# ATMega328P_weather_station_MCU.net
KiCad netlist of a schematic drawn in Altium Designer
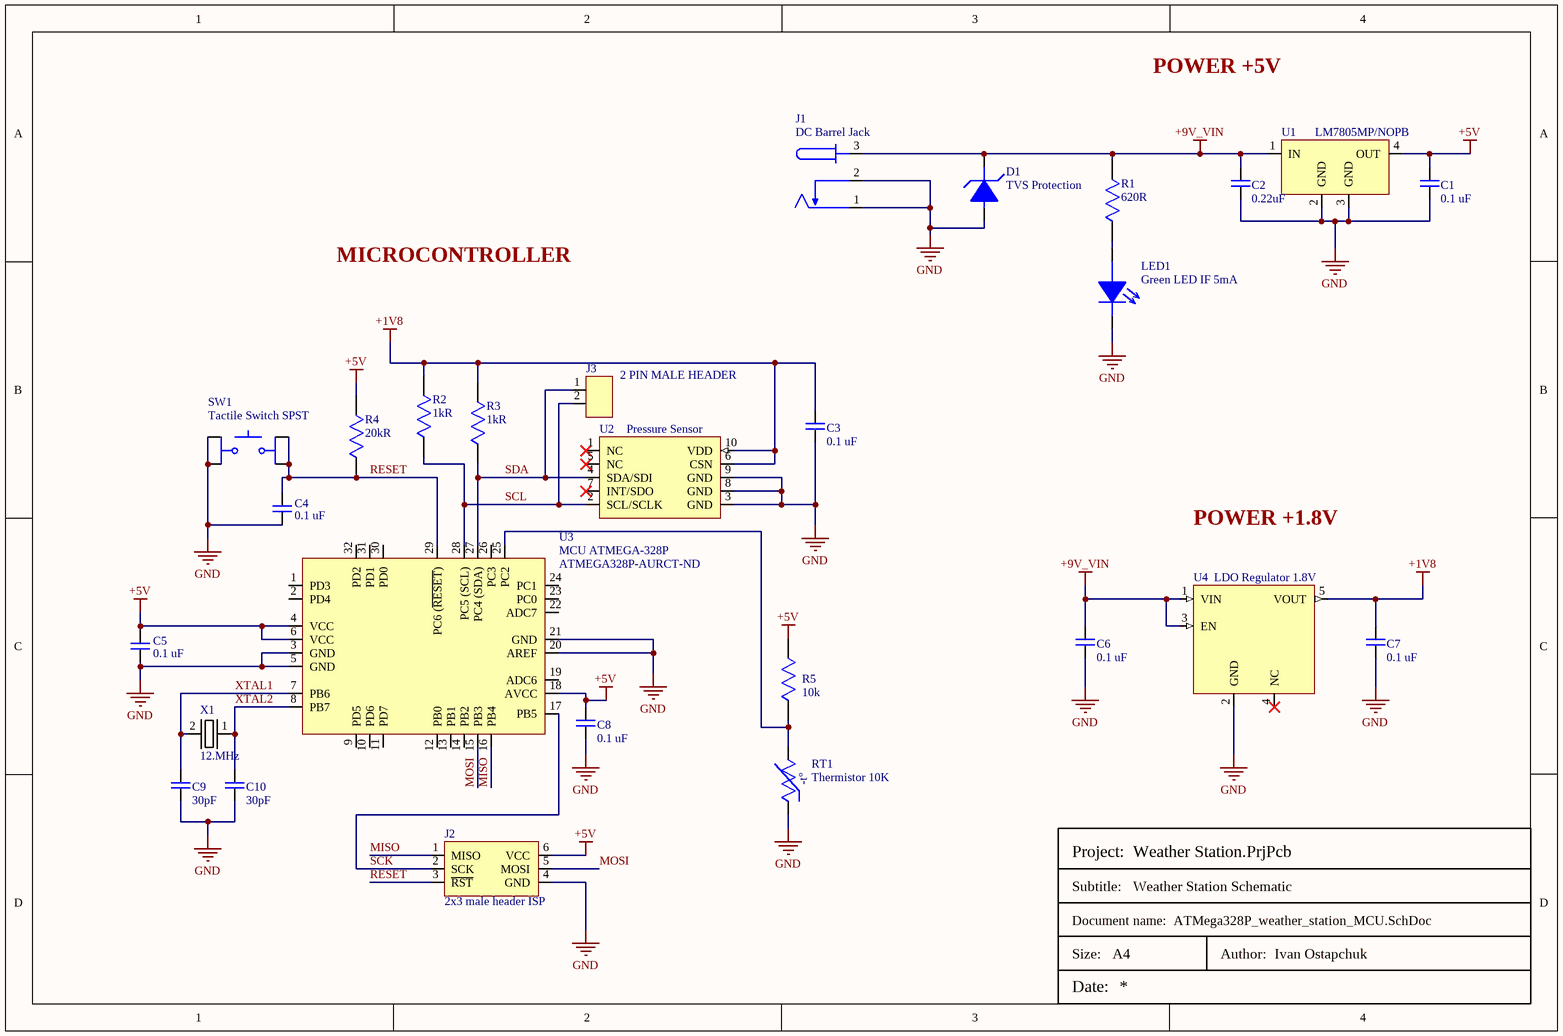
[diagram p0: ATMega328P_weather_station_MCU.SchDoc]

(export (version "E")
  (design (tool "Eeschema 10.0.6"))
  (components
    (comp (ref "*")
      (value "Title Block")
      (description "Custom schematic title block")
      (fields (field (name "SUBTITLE") "Weather Station Schematic") (field (name "SIZE") "A4"))
      (libsource (lib "Weather_Schlib") (part "Title Block"))
    )
    (comp (ref "C1")
      (value "0.1 uF")
      (footprint "1210B104K500CT")
      (fields
        (field (name "MANUFACTURER") "Walsin Technologies")
        (field (name "MANUFACTURER PART NUMBER") "1210B104K500CT")
        (field (name "TOLERANCE") "10%")
      )
      (libsource (lib "Weather_Schlib") (part "Ceramic Cap, 0.1 uF, 10%, 50 V, 1210"))
    )
    (comp (ref "C2")
      (value "0.22uF")
      (footprint "Ceramic Cap 0.22uF 1210 Low density")
      (description "Multilayer Ceramic Capacitors MLCC - SMD/SMT 50V 0.22uF X7R 1210 10%")
      (fields
        (field (name "MANUFACTURER") "KEMET")
        (field (name "MANUFACTURER PART NUMBER") "C1210C224K5RACTU")
      )
      (libsource (lib "Weather_Schlib") (part "Ceramic Cap, 0.22uF, 10%, 50V, 1210"))
    )
    (comp (ref "C3")
      (value "0.1 uF")
      (footprint "1210B104K500CT")
      (fields
        (field (name "MANUFACTURER") "Walsin Technologies")
        (field (name "MANUFACTURER PART NUMBER") "1210B104K500CT")
        (field (name "TOLERANCE") "10%")
      )
      (libsource (lib "Weather_Schlib") (part "Ceramic Cap, 0.1 uF, 10%, 50 V, 1210"))
    )
    (comp (ref "C4")
      (value "0.1 uF")
      (footprint "1210B104K500CT")
      (fields
        (field (name "MANUFACTURER") "Walsin Technologies")
        (field (name "MANUFACTURER PART NUMBER") "1210B104K500CT")
        (field (name "TOLERANCE") "10%")
      )
      (libsource (lib "Weather_Schlib") (part "Ceramic Cap, 0.1 uF, 10%, 50 V, 1210"))
    )
    (comp (ref "C5")
      (value "0.1 uF")
      (footprint "1210B104K500CT")
      (fields
        (field (name "MANUFACTURER") "Walsin Technologies")
        (field (name "MANUFACTURER PART NUMBER") "1210B104K500CT")
        (field (name "TOLERANCE") "10%")
      )
      (libsource (lib "Weather_Schlib") (part "Ceramic Cap, 0.1 uF, 10%, 50 V, 1210"))
    )
    (comp (ref "C6")
      (value "0.1 uF")
      (footprint "1210B104K500CT")
      (fields
        (field (name "MANUFACTURER") "Walsin Technologies")
        (field (name "MANUFACTURER PART NUMBER") "1210B104K500CT")
        (field (name "TOLERANCE") "10%")
      )
      (libsource (lib "Weather_Schlib") (part "Ceramic Cap, 0.1 uF, 10%, 50 V, 1210"))
    )
    (comp (ref "C7")
      (value "0.1 uF")
      (footprint "1210B104K500CT")
      (fields
        (field (name "MANUFACTURER") "Walsin Technologies")
        (field (name "MANUFACTURER PART NUMBER") "1210B104K500CT")
        (field (name "TOLERANCE") "10%")
      )
      (libsource (lib "Weather_Schlib") (part "Ceramic Cap, 0.1 uF, 10%, 50 V, 1210"))
    )
    (comp (ref "C8")
      (value "0.1 uF")
      (footprint "1210B104K500CT")
      (fields
        (field (name "MANUFACTURER") "Walsin Technologies")
        (field (name "MANUFACTURER PART NUMBER") "1210B104K500CT")
        (field (name "TOLERANCE") "10%")
      )
      (libsource (lib "Weather_Schlib") (part "Ceramic Cap, 0.1 uF, 10%, 50 V, 1210"))
    )
    (comp (ref "C9")
      (value "30pF")
      (footprint "Kyocera 1210 Ceramic Capacitor")
      (description "30 pF ±5% 200V Ceramic Capacitor C0G, NP0 1210 (3225 Metric)")
      (fields
        (field (name "MANUFACTURER") "Kyocera AVX")
        (field (name "MANUFACTURER PART NUMBER") "KGQ32DCG2D300JT")
      )
      (libsource (lib "Weather_Schlib") (part "Ceramic Cap, 30pF, ±5%, 200V, 1210"))
    )
    (comp (ref "C10")
      (value "30pF")
      (footprint "Kyocera 1210 Ceramic Capacitor")
      (description "30 pF ±5% 200V Ceramic Capacitor C0G, NP0 1210 (3225 Metric)")
      (fields
        (field (name "MANUFACTURER") "Kyocera AVX")
        (field (name "MANUFACTURER PART NUMBER") "KGQ32DCG2D300JT")
      )
      (libsource (lib "Weather_Schlib") (part "Ceramic Cap, 30pF, ±5%, 200V, 1210"))
    )
    (comp (ref "D1")
      (value "TVS Protection")
      (footprint "Unidirectional TVS protection diode")
      (fields (field (name "MANUFACTURER") "Littelfuse") (field (name "MANUFACTURER PART NUMBER") "SMAJ10A"))
      (libsource (lib "Weather_Schlib") (part "Unidirectional TVS protection Diode"))
    )
    (comp (ref "J1")
      (value "DC Barrel Jack")
      (footprint "Power Barrel Jack")
      (description "Power Barrel Connector Jack 2.05mm ID (0.081\"), 5.50mm OD (0.217\") Surface Mount, Right Angle")
      (fields
        (field (name "MANUFACTURER") "Global Connector Technology")
        (field (name "MANUFACTURER PART NUMBER") "DCJ200-05-A-K1-A")
      )
      (libsource (lib "Weather_Schlib") (part "Barrel Connector Jack"))
    )
    (comp (ref "J2")
      (value "2x3 male header ISP")
      (footprint "2x3 male header ISP")
      (description "Bs Dr Vt SMT Hdr 2X3 TR-10125394-T0803ALF ¦ Amphenol Fci (amphenol Cs) 10125394T0803ALF")
      (fields
        (field (name "MANUFACTURER") "Amphenol Communications Solutions")
        (field (name "MANUFACTURER PART NUMBER") "10125394-T0803ALF")
      )
      (libsource (lib "Weather_Schlib") (part "2x3 male header ISP"))
    )
    (comp (ref "J3")
      (value "2 PIN MALE HEADER")
      (footprint "2 pin male header smd")
      (description "Conn Unshrouded Header HDR 2 POS 2.54mm Solder ST SMD Automotive T/R")
      (fields
        (field (name "MANUFACTURER") "Samtec")
        (field (name "MANUFACTURER PART NUMBER") "TSM-102-01-T-SV-TR")
      )
      (libsource (lib "Weather_Schlib") (part "2 pin male header"))
    )
    (comp (ref "LED1")
      (value "Green LED IF 5mA")
      (footprint "SMD LED")
      (description "Side View / 0805 / 2.1 X 1.0 X 0")
      (fields (field (name "MANUFACTURER") "Inolux") (field (name "MANUFACTURER PART NUMBER") "IN-S85CS5G"))
      (libsource (lib "Weather_Schlib") (part "Green LED IF 5mA"))
    )
    (comp (ref "R1")
      (value "620R")
      (footprint "1206 WIDE SMD Resistor")
      (fields
        (field (name "MANUFACTURER") "Rohm")
        (field (name "MANUFACTURER PART NUMBER") "LTR18EZPF6200")
        (field (name "TOLERANCE") "1%")
      )
      (libsource (lib "Weather_Schlib") (part "SMD Resistor 620 Ohms, 1.5W 1206 WIDE"))
    )
    (comp (ref "R2")
      (value "1kR")
      (footprint "Yageo 1206 SMD Resistor")
      (description "SMD Chip Resistor, 1 kOhm, ± 1%, 250 mW, 1206 [3216 Metric], Thick Film, General Purpose")
      (fields
        (field (name "MANUFACTURER") "Yageo")
        (field (name "MANUFACTURER PART NUMBER") "RC1206FR-071KL")
      )
      (libsource (lib "Weather_Schlib") (part "SMD Resistor 1 kOhm, 250mW, 1206"))
    )
    (comp (ref "R3")
      (value "1kR")
      (footprint "Yageo 1206 SMD Resistor")
      (description "SMD Chip Resistor, 1 kOhm, ± 1%, 250 mW, 1206 [3216 Metric], Thick Film, General Purpose")
      (fields
        (field (name "MANUFACTURER") "Yageo")
        (field (name "MANUFACTURER PART NUMBER") "RC1206FR-071KL")
      )
      (libsource (lib "Weather_Schlib") (part "SMD Resistor 1 kOhm, 250mW, 1206"))
    )
    (comp (ref "R4")
      (value "20kR")
      (footprint "Yageo 1206 SMD Resistor")
      (description "20 kOhm, ± 1%, 250 mW, SMD Resistor, 1206 [3216 Metric], Thick Film, General Purpose")
      (fields
        (field (name "MANUFACTURER") "Yageo")
        (field (name "MANUFACTURER PART NUMBER") "RC1206FR-0720KL")
      )
      (libsource (lib "Weather_Schlib") (part "SMD Resistor, 20k Ohm, 250mW, 1206"))
    )
    (comp (ref "R5")
      (value "10k")
      (footprint "Yageo 1206 SMD Resistor")
      (description "SMD Chip Resistor, 10 kOhm, 1%, 250 mW, 1206 [3216 Metric], Thick Film, General Purpose")
      (fields
        (field (name "MANUFACTURER") "Yageo")
        (field (name "MANUFACTURER PART NUMBER") "RC1206FR-0710KL")
      )
      (libsource (lib "Weather_Schlib") (part "SMD Resistor, 10 kOhm, 250 mW, 1206"))
    )
    (comp (ref "RT1")
      (value "Thermistor 10K")
      (footprint "Yageo 1206 SMD Resistor")
      (description "Thermistor NTC 10K Ohm 10% 2-Pin 1206 Surface Mount Solder Pad 3510K Blister T/R")
      (fields
        (field (name "MANUFACTURER") "TDK EPCOS")
        (field (name "MANUFACTURER PART NUMBER") "B57621C5103K062")
      )
      (libsource (lib "Weather_Schlib") (part "Thermistor NTC 10K"))
    )
    (comp (ref "SW1")
      (value "Tactile Switch SPST")
      (footprint "Tactile Switch")
      (description "TL3305A Series SPST 12 V 4.5 x 4.5 mm 260 gf Top Actuated SMT Tactile Switch")
      (fields
        (field (name "MANUFACTURER") "E-Switch")
        (field (name "MANUFACTURER PART NUMBER") "TL3305AF260QG")
      )
      (libsource (lib "Weather_Schlib") (part "Tactile Switch SPST"))
    )
    (comp (ref "U1")
      (value "Linear V Regulator")
      (footprint "LM7805MP/NOPB")
      (description "1.5-A, 30-V, linear voltage regulator 4-SOT-223 0 to 125")
      (fields
        (field (name "MANUFACTURER") "Texas Instruments")
        (field (name "MANUFACTURER PART NUMBER") "LM7805MP/NOPB")
      )
      (libsource (lib "Weather_Schlib") (part "Linear Voltage Regulator LM7805MP/NOPB"))
    )
    (comp (ref "U2")
      (value "Pressure Sensor")
      (footprint "XDCR_ENS220S-BLGT")
      (description "Pressure Sensor 4.35PSI ~ 17.4PSI (30kPa ~ 120kPa) Absolute 24 b 10-LGA")
      (fields
        (field (name "MANUFACTURER") "ScioSense")
        (field (name "MANUFACTURER PART NUMBER") "ENS220S-BLGT")
      )
      (libsource (lib "Weather_Schlib") (part "Pressure Sensor"))
    )
    (comp (ref "U3")
      (value "MCU ATMEGA-328P")
      (footprint "QFP80P900X900X120-32N")
      (description "AVR series Microcontroller IC 8-Bit 2MHz 32KB (16K x 16) FLASH 32-TQFP (7x7)")
      (fields
        (field (name "MANUFACTURER") "Microchip")
        (field (name "MANUFACTURER PART NUMBER") "ATMEGA328P-AUR")
        (field (name "SUPPLIER PART NUMBER 1") "ATMEGA328P-AURCT-ND")
      )
      (libsource (lib "Weather_Schlib") (part "MCU ATMEGA-328P"))
    )
    (comp (ref "U4")
      (value "LDO Regulator 1.8V")
      (footprint "LDO 1.8V")
      (description "Linear Voltage Regulator IC Positive Fixed 1 Output 1.8V 300mA SOT-23-5")
      (fields
        (field (name "MANUFACTURER") "Microchip")
        (field (name "MANUFACTURER PART NUMBER") "MIC5504-1.8YM5-TR")
      )
      (libsource (lib "Weather_Schlib") (part "LDO Regulator 1.8V"))
    )
    (comp (ref "X1")
      (value "12.MHz")
      (footprint "ABLS-12.000MHZ-20-B-3-H-T")
      (description "Crystal 12MHz ±25ppm (Tol) ±35ppm (Stability) 20pF FUND 50Ohm 2-Pin HC-49/US SMD T/R")
      (fields
        (field (name "MANUFACTURER") "Abracon")
        (field (name "MANUFACTURER PART NUMBER") "ABLS-12.000MHZ-20-B-3-H-T")
      )
      (libsource (lib "Weather_Schlib") (part "ABLS-12.000MHZ-20-B-3-H-T"))
    )
  )
  (nets
    (net (code "1") (name "+1V8") (class "Default")
      (node (ref "C3") (pin "2") (pinfunction "2_2") (pintype "passive"))
      (node (ref "C7") (pin "1") (pinfunction "1_1") (pintype "passive"))
      (node (ref "R2") (pin "1") (pinfunction "1_1") (pintype "passive"))
      (node (ref "R3") (pin "1") (pinfunction "1_1") (pintype "passive"))
      (node (ref "U2") (pin "10") (pinfunction "VDD_10") (pintype "input"))
      (node (ref "U2") (pin "6") (pinfunction "CSN_6") (pintype "passive"))
      (node (ref "U4") (pin "5") (pinfunction "VOUT_5") (pintype "output"))
    )
    (net (code "2") (name "+5V") (class "Default")
      (node (ref "C1") (pin "1") (pinfunction "1_1") (pintype "passive"))
      (node (ref "C5") (pin "2") (pinfunction "2_2") (pintype "passive"))
      (node (ref "C8") (pin "2") (pinfunction "2_2") (pintype "passive"))
      (node (ref "J2") (pin "6") (pinfunction "VCC_6") (pintype "passive"))
      (node (ref "R4") (pin "1") (pinfunction "1_1") (pintype "passive"))
      (node (ref "R5") (pin "1") (pinfunction "1_1") (pintype "passive"))
      (node (ref "U1") (pin "4") (pinfunction "OUT_4") (pintype "passive"))
      (node (ref "U3") (pin "18") (pinfunction "AVCC_18") (pintype "passive"))
      (node (ref "U3") (pin "4") (pinfunction "VCC_4") (pintype "passive"))
      (node (ref "U3") (pin "6") (pinfunction "VCC_6") (pintype "passive"))
    )
    (net (code "3") (name "+9V_VIN") (class "Default")
      (node (ref "C2") (pin "1") (pinfunction "1_1") (pintype "passive"))
      (node (ref "C6") (pin "1") (pinfunction "1_1") (pintype "passive"))
      (node (ref "D1") (pin "2") (pinfunction "2_2") (pintype "passive"))
      (node (ref "J1") (pin "3") (pinfunction "CENTER_(V+)_3") (pintype "power_in"))
      (node (ref "R1") (pin "2") (pinfunction "2_2") (pintype "passive"))
      (node (ref "U1") (pin "1") (pinfunction "IN_1") (pintype "passive"))
      (node (ref "U4") (pin "1") (pinfunction "VIN_1") (pintype "input"))
      (node (ref "U4") (pin "3") (pinfunction "EN_3") (pintype "input"))
    )
    (net (code "4") (name "/MISO") (class "Default")
      (node (ref "J2") (pin "1") (pinfunction "MISO_1") (pintype "passive"))
      (node (ref "U3") (pin "16") (pinfunction "PB4_16") (pintype "passive"))
    )
    (net (code "5") (name "/MOSI") (class "Default")
      (node (ref "J2") (pin "5") (pinfunction "MOSI_5") (pintype "passive"))
      (node (ref "U3") (pin "15") (pinfunction "PB3_15") (pintype "passive"))
    )
    (net (code "6") (name "/RESET") (class "Default")
      (node (ref "C4") (pin "2") (pinfunction "2_2") (pintype "passive"))
      (node (ref "J2") (pin "3") (pinfunction "~{RST}_3") (pintype "passive"))
      (node (ref "R4") (pin "2") (pinfunction "2_2") (pintype "passive"))
      (node (ref "SW1") (pin "2") (pinfunction "2_2") (pintype "passive"))
      (node (ref "SW1") (pin "4") (pinfunction "4_4") (pintype "passive"))
      (node (ref "U3") (pin "29") (pinfunction "PC6_(~{RESET})_29") (pintype "passive"))
    )
    (net (code "7") (name "/SCK") (class "Default")
      (node (ref "J2") (pin "2") (pinfunction "SCK_2") (pintype "passive"))
      (node (ref "U3") (pin "17") (pinfunction "PB5_17") (pintype "passive"))
    )
    (net (code "8") (name "/SCL") (class "Default")
      (node (ref "J3") (pin "2") (pintype "passive"))
      (node (ref "R2") (pin "2") (pinfunction "2_2") (pintype "passive"))
      (node (ref "U2") (pin "2") (pinfunction "SCL/SCLK_2") (pintype "passive"))
      (node (ref "U3") (pin "28") (pinfunction "PC5_(SCL)_28") (pintype "passive"))
    )
    (net (code "9") (name "/SDA") (class "Default")
      (node (ref "J3") (pin "1") (pintype "passive"))
      (node (ref "R3") (pin "2") (pinfunction "2_2") (pintype "passive"))
      (node (ref "U2") (pin "4") (pinfunction "SDA/SDI_4") (pintype "passive"))
      (node (ref "U3") (pin "27") (pinfunction "PC4_(SDA)_27") (pintype "passive"))
    )
    (net (code "10") (name "/XTAL1") (class "Default")
      (node (ref "C9") (pin "2") (pinfunction "2_2") (pintype "passive"))
      (node (ref "U3") (pin "7") (pinfunction "PB6_7") (pintype "passive"))
      (node (ref "X1") (pin "2") (pinfunction "2_2") (pintype "passive"))
    )
    (net (code "11") (name "/XTAL2") (class "Default")
      (node (ref "C10") (pin "2") (pinfunction "2_2") (pintype "passive"))
      (node (ref "U3") (pin "8") (pinfunction "PB7_8") (pintype "passive"))
      (node (ref "X1") (pin "1") (pinfunction "1_1") (pintype "passive"))
    )
    (net (code "12") (name "GND") (class "Default")
      (node (ref "C1") (pin "2") (pinfunction "2_2") (pintype "passive"))
      (node (ref "C10") (pin "1") (pinfunction "1_1") (pintype "passive"))
      (node (ref "C2") (pin "2") (pinfunction "2_2") (pintype "passive"))
      (node (ref "C3") (pin "1") (pinfunction "1_1") (pintype "passive"))
      (node (ref "C4") (pin "1") (pinfunction "1_1") (pintype "passive"))
      (node (ref "C5") (pin "1") (pinfunction "1_1") (pintype "passive"))
      (node (ref "C6") (pin "2") (pinfunction "2_2") (pintype "passive"))
      (node (ref "C7") (pin "2") (pinfunction "2_2") (pintype "passive"))
      (node (ref "C8") (pin "1") (pinfunction "1_1") (pintype "passive"))
      (node (ref "C9") (pin "1") (pinfunction "1_1") (pintype "passive"))
      (node (ref "D1") (pin "1") (pinfunction "1_1") (pintype "passive"))
      (node (ref "J1") (pin "1") (pinfunction "GND_1") (pintype "passive"))
      (node (ref "J1") (pin "2") (pinfunction "SPRING_(GND)_2") (pintype "passive"))
      (node (ref "J2") (pin "4") (pinfunction "GND_4") (pintype "passive"))
      (node (ref "LED1") (pin "2") (pinfunction "2_2") (pintype "passive"))
      (node (ref "RT1") (pin "1") (pinfunction "1_1") (pintype "passive"))
      (node (ref "SW1") (pin "1") (pinfunction "1_1") (pintype "passive"))
      (node (ref "SW1") (pin "3") (pinfunction "3_3") (pintype "passive"))
      (node (ref "U1") (pin "2") (pinfunction "GND_2") (pintype "passive"))
      (node (ref "U1") (pin "3") (pinfunction "GND_3") (pintype "passive"))
      (node (ref "U2") (pin "3") (pinfunction "GND_3") (pintype "passive"))
      (node (ref "U2") (pin "8") (pinfunction "GND_8") (pintype "passive"))
      (node (ref "U2") (pin "9") (pinfunction "GND_9") (pintype "passive"))
      (node (ref "U3") (pin "20") (pinfunction "AREF_20") (pintype "passive"))
      (node (ref "U3") (pin "21") (pinfunction "GND_21") (pintype "passive"))
      (node (ref "U3") (pin "3") (pinfunction "GND_3") (pintype "passive"))
      (node (ref "U3") (pin "5") (pinfunction "GND_5") (pintype "passive"))
      (node (ref "U4") (pin "2") (pinfunction "GND_2") (pintype "passive"))
    )
    (net (code "13") (name "Net-(LED1-Pad1)") (class "Default")
      (node (ref "LED1") (pin "1") (pinfunction "1_1") (pintype "passive"))
      (node (ref "R1") (pin "1") (pinfunction "1_1") (pintype "passive"))
    )
    (net (code "14") (name "Net-(U3-PC2)") (class "Default")
      (node (ref "R5") (pin "2") (pinfunction "2_2") (pintype "passive"))
      (node (ref "RT1") (pin "2") (pinfunction "2_2") (pintype "passive"))
      (node (ref "U3") (pin "25") (pinfunction "PC2_25") (pintype "passive"))
    )
    (net (code "15") (name "unconnected-(U2-INT{slash}SDO-Pad7)") (class "Default")
      (node (ref "U2") (pin "7") (pinfunction "INT/SDO_7") (pintype "passive+no_connect"))
    )
    (net (code "16") (name "unconnected-(U2-NC-Pad1)") (class "Default")
      (node (ref "U2") (pin "1") (pinfunction "NC_1") (pintype "passive+no_connect"))
    )
    (net (code "17") (name "unconnected-(U2-NC-Pad5)") (class "Default")
      (node (ref "U2") (pin "5") (pinfunction "NC_5") (pintype "passive+no_connect"))
    )
    (net (code "18") (name "unconnected-(U3-ADC6-Pad19)") (class "Default")
      (node (ref "U3") (pin "19") (pinfunction "ADC6_19") (pintype "passive"))
    )
    (net (code "19") (name "unconnected-(U3-ADC7-Pad22)") (class "Default")
      (node (ref "U3") (pin "22") (pinfunction "ADC7_22") (pintype "passive"))
    )
    (net (code "20") (name "unconnected-(U3-PB0-Pad12)") (class "Default")
      (node (ref "U3") (pin "12") (pinfunction "PB0_12") (pintype "passive"))
    )
    (net (code "21") (name "unconnected-(U3-PB1-Pad13)") (class "Default")
      (node (ref "U3") (pin "13") (pinfunction "PB1_13") (pintype "passive"))
    )
    (net (code "22") (name "unconnected-(U3-PB2-Pad14)") (class "Default")
      (node (ref "U3") (pin "14") (pinfunction "PB2_14") (pintype "passive"))
    )
    (net (code "23") (name "unconnected-(U3-PC0-Pad23)") (class "Default")
      (node (ref "U3") (pin "23") (pinfunction "PC0_23") (pintype "passive"))
    )
    (net (code "24") (name "unconnected-(U3-PC1-Pad24)") (class "Default")
      (node (ref "U3") (pin "24") (pinfunction "PC1_24") (pintype "passive"))
    )
    (net (code "25") (name "unconnected-(U3-PC3-Pad26)") (class "Default")
      (node (ref "U3") (pin "26") (pinfunction "PC3_26") (pintype "passive"))
    )
    (net (code "26") (name "unconnected-(U3-PD0-Pad30)") (class "Default")
      (node (ref "U3") (pin "30") (pinfunction "PD0_30") (pintype "passive"))
    )
    (net (code "27") (name "unconnected-(U3-PD1-Pad31)") (class "Default")
      (node (ref "U3") (pin "31") (pinfunction "PD1_31") (pintype "power_in"))
    )
    (net (code "28") (name "unconnected-(U3-PD2-Pad32)") (class "Default")
      (node (ref "U3") (pin "32") (pinfunction "PD2_32") (pintype "power_in"))
    )
    (net (code "29") (name "unconnected-(U3-PD3-Pad1)") (class "Default")
      (node (ref "U3") (pin "1") (pinfunction "PD3_1") (pintype "power_in"))
    )
    (net (code "30") (name "unconnected-(U3-PD4-Pad2)") (class "Default")
      (node (ref "U3") (pin "2") (pinfunction "PD4_2") (pintype "power_in"))
    )
    (net (code "31") (name "unconnected-(U3-PD5-Pad9)") (class "Default")
      (node (ref "U3") (pin "9") (pinfunction "PD5_9") (pintype "passive"))
    )
    (net (code "32") (name "unconnected-(U3-PD6-Pad10)") (class "Default")
      (node (ref "U3") (pin "10") (pinfunction "PD6_10") (pintype "passive"))
    )
    (net (code "33") (name "unconnected-(U3-PD7-Pad11)") (class "Default")
      (node (ref "U3") (pin "11") (pinfunction "PD7_11") (pintype "passive"))
    )
    (net (code "34") (name "unconnected-(U4-NC-Pad4)") (class "Default")
      (node (ref "U4") (pin "4") (pinfunction "NC_4") (pintype "passive+no_connect"))
    )
  )
)
